# SBC_Interface.net
KiCad netlist of a schematic drawn in Altium Designer
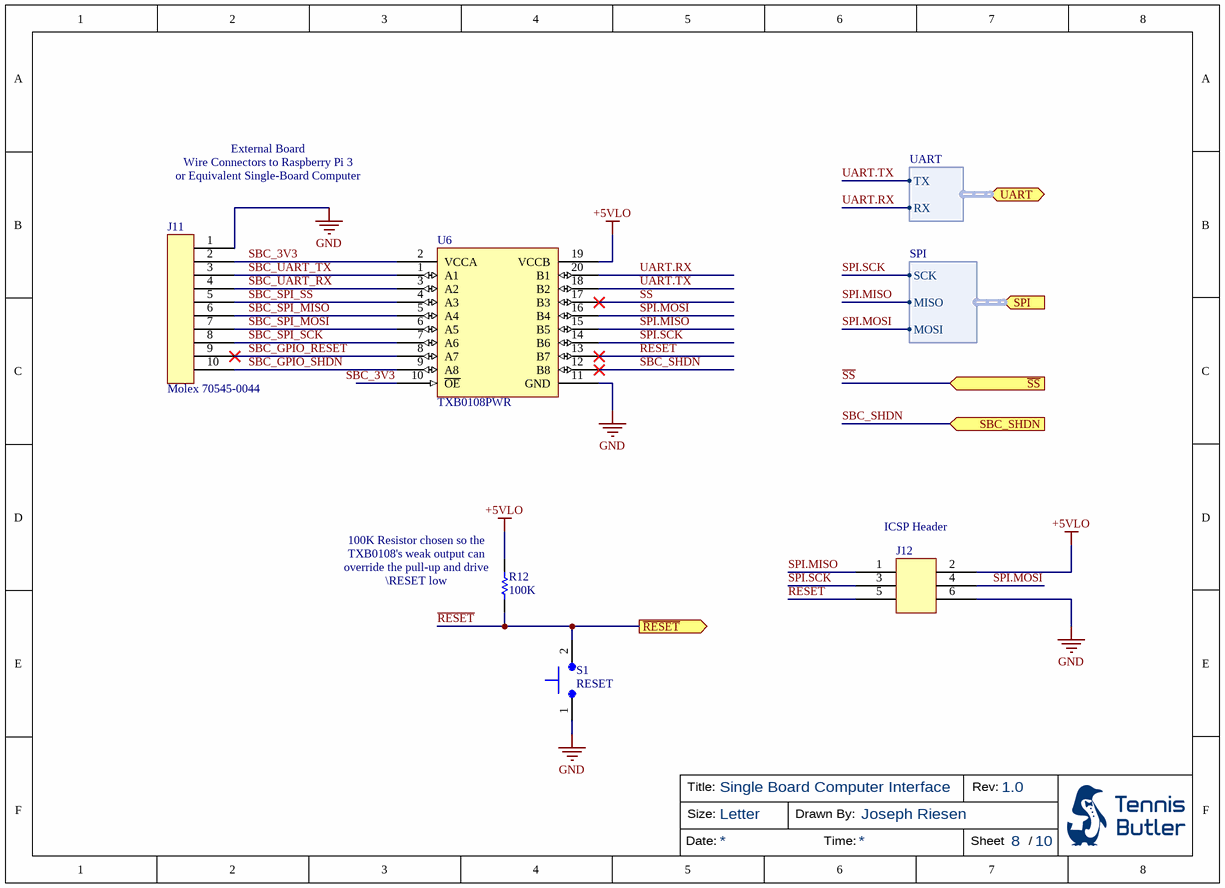
[diagram p0: SBC Interface.SchDoc]

(export (version "E")
  (design (tool "Eeschema 10.0.6"))
  (components
    (comp (ref "J11")
      (value "Molex 70545-0044")
      (footprint "Molex 70545-0044")
      (description "CONN HEADER VERT 10POS 2.54MM, PEG")
      (fields (field (name "MANUFACTURER") "Molex") (field (name "MANUFACTURER PART NUMBER") "70545-0044"))
      (libsource (lib "TennisButler") (part "Molex 70545-0044 SL 10-Pin Header"))
    )
    (comp (ref "J12")
      (value "ICSP")
      (footprint "Molex 70287-1099")
      (description "CONN HEADER BKWY DL GOLD 6POS")
      (fields (field (name "MANUFACTURER") "Molex") (field (name "MANUFACTURER PART NUMBER") "0702871099"))
      (libsource (lib "TennisButler") (part "Molex 70287-1099 6-Pin (3x2) Male Header"))
    )
    (comp (ref "R12")
      (value "100K")
      (footprint "RESC2013X70X40ML20T20")
      (description "RES SMD 100K OHM 1% 1/8W 0805")
      (fields (field (name "PART NUMBER") "ERJ-6ENF1003V") (field (name "MANUFACTURER") "Panasonic"))
      (libsource (lib "Altium Content Vault") (part "RES"))
    )
    (comp (ref "S1")
      (value "RESET")
      (footprint "E-Switch TL9210 Series Tact Switch")
      (description "SWITCH TACTILE SPST-NO 0.05A 12V")
      (fields
        (field (name "MANUFACTURER") "E-Switch")
        (field (name "MANUFACTURER PART NUMBER") "TL9210AF260Q")
      )
      (libsource (lib "Buttons") (part "E-Switch TL9210 Series Tact Switch"))
    )
    (comp (ref "U6")
      (value "TXB0108PWR")
      (footprint "TSOP65P640X120-20M")
      (description "IC, TRANSLATOR, 8BIT, BIDIRECTIONAL")
      (fields (field (name "MANUFACTURER") "Texas Instruments"))
      (libsource (lib "TXB0108") (part "TXB0108PWR"))
    )
  )
  (nets
    (net (code "3") (name "+5VLO") (class "Default")
      (node (ref "J12") (pin "2") (pintype "passive"))
      (node (ref "R12") (pin "2") (pinfunction "2_2") (pintype "passive"))
      (node (ref "U6") (pin "19") (pinfunction "VCCB_19") (pintype "power_in"))
    )
    (net (code "4") (name "/SBC_3V3") (class "Default")
      (node (ref "J11") (pin "2") (pintype "passive"))
      (node (ref "U6") (pin "10") (pinfunction "~{OE}_10") (pintype "input"))
      (node (ref "U6") (pin "2") (pinfunction "VCCA_2") (pintype "power_in"))
    )
    (net (code "5") (name "/SBC_GPIO_RESET") (class "Default")
      (node (ref "J11") (pin "9") (pintype "passive"))
      (node (ref "U6") (pin "8") (pinfunction "A7_8") (pintype "bidirectional"))
    )
    (net (code "6") (name "/SBC_GPIO_SHDN") (class "Default")
      (node (ref "J11") (pin "10") (pintype "passive"))
      (node (ref "U6") (pin "9") (pinfunction "A8_9") (pintype "bidirectional"))
    )
    (net (code "7") (name "/SBC_SHDN") (class "Default")
      (node (ref "U6") (pin "12") (pinfunction "B8_12") (pintype "bidirectional"))
    )
    (net (code "8") (name "/SBC_SPI_MISO") (class "Default")
      (node (ref "J11") (pin "6") (pintype "passive"))
      (node (ref "U6") (pin "5") (pinfunction "A4_5") (pintype "bidirectional"))
    )
    (net (code "9") (name "/SBC_SPI_MOSI") (class "Default")
      (node (ref "J11") (pin "7") (pintype "passive"))
      (node (ref "U6") (pin "6") (pinfunction "A5_6") (pintype "bidirectional"))
    )
    (net (code "10") (name "/SBC_SPI_SCK") (class "Default")
      (node (ref "J11") (pin "8") (pintype "passive"))
      (node (ref "U6") (pin "7") (pinfunction "A6_7") (pintype "bidirectional"))
    )
    (net (code "11") (name "/SBC_SPI_SS") (class "Default")
      (node (ref "J11") (pin "5") (pintype "passive"))
      (node (ref "U6") (pin "4") (pinfunction "A3_4") (pintype "bidirectional"))
    )
    (net (code "12") (name "/SBC_UART_RX") (class "Default")
      (node (ref "J11") (pin "4") (pintype "passive"))
      (node (ref "U6") (pin "3") (pinfunction "A2_3") (pintype "bidirectional"))
    )
    (net (code "13") (name "/SBC_UART_TX") (class "Default")
      (node (ref "J11") (pin "3") (pintype "passive"))
      (node (ref "U6") (pin "1") (pinfunction "A1_1") (pintype "bidirectional"))
    )
    (net (code "14") (name "/SPI.MISO") (class "Default")
      (node (ref "J12") (pin "1") (pintype "passive"))
      (node (ref "U6") (pin "15") (pinfunction "B5_15") (pintype "bidirectional"))
    )
    (net (code "15") (name "/SPI.MOSI") (class "Default")
      (node (ref "J12") (pin "4") (pintype "passive"))
      (node (ref "U6") (pin "16") (pinfunction "B4_16") (pintype "bidirectional"))
    )
    (net (code "16") (name "/SPI.SCK") (class "Default")
      (node (ref "J12") (pin "3") (pintype "passive"))
      (node (ref "U6") (pin "14") (pinfunction "B6_14") (pintype "bidirectional"))
    )
    (net (code "17") (name "/UART.RX") (class "Default")
      (node (ref "U6") (pin "20") (pinfunction "B1_20") (pintype "bidirectional"))
    )
    (net (code "18") (name "/UART.TX") (class "Default")
      (node (ref "U6") (pin "18") (pinfunction "B2_18") (pintype "bidirectional"))
    )
    (net (code "21") (name "/~{RESET}") (class "Default")
      (node (ref "J12") (pin "5") (pintype "passive"))
      (node (ref "R12") (pin "1") (pinfunction "1_1") (pintype "passive"))
      (node (ref "S1") (pin "2") (pintype "passive"))
      (node (ref "U6") (pin "13") (pinfunction "B7_13") (pintype "bidirectional"))
    )
    (net (code "22") (name "/~{SS}") (class "Default")
      (node (ref "U6") (pin "17") (pinfunction "B3_17") (pintype "bidirectional+no_connect"))
    )
    (net (code "23") (name "GND") (class "Default")
      (node (ref "J11") (pin "1") (pintype "passive"))
      (node (ref "J12") (pin "6") (pintype "passive"))
      (node (ref "S1") (pin "1") (pintype "passive"))
      (node (ref "U6") (pin "11") (pinfunction "GND_11") (pintype "power_in"))
    )
  )
)
